# Soic8Pads.net
KiCad netlist of a schematic drawn in Altium Designer
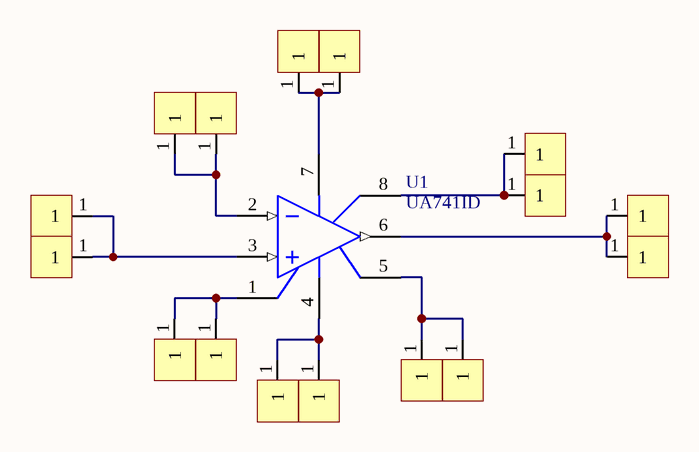
[diagram p0: Soic8Pads.SchDoc]

(export (version "E")
  (design (tool "Eeschema 10.0.6"))
  (components
    (comp (ref "U1")
      (value "UA741ID")
      (footprint "SO8_N")
      (description "General-Purpose Single Operational Amplifier")
      (fields (field (name "PUBLISHER") "Altium Limited"))
      (libsource (lib "ST Operational Amplifier") (part "UA741ID"))
    )
    (comp (ref "V5")
      (value "VIA40mil80mil")
      (footprint "VIA40mil80mil")
      (libsource (lib "") (part "VIA40mil80mil_2"))
    )
    (comp (ref "V6")
      (value "VIA40mil80mil")
      (footprint "VIA40mil80mil")
      (libsource (lib "") (part "VIA40mil80mil_2"))
    )
    (comp (ref "V9")
      (value "VIA40mil80mil")
      (footprint "VIA40mil80mil")
      (libsource (lib "") (part "VIA40mil80mil_2"))
    )
    (comp (ref "V10")
      (value "VIA40mil80mil")
      (footprint "VIA40mil80mil")
      (libsource (lib "") (part "VIA40mil80mil_2"))
    )
    (comp (ref "V13")
      (value "VIA40mil80mil")
      (footprint "VIA40mil80mil")
      (libsource (lib "") (part "VIA40mil80mil_1"))
    )
    (comp (ref "V15")
      (value "VIA40mil80mil")
      (footprint "VIA40mil80mil")
      (libsource (lib "") (part "VIA40mil80mil_1"))
    )
    (comp (ref "V17")
      (value "VIA40mil80mil")
      (footprint "VIA40mil80mil")
      (libsource (lib "") (part "VIA40mil80mil_3"))
    )
    (comp (ref "V18")
      (value "VIA40mil80mil")
      (footprint "VIA40mil80mil")
      (libsource (lib "") (part "VIA40mil80mil_1"))
    )
    (comp (ref "V21")
      (value "VIA40mil80mil")
      (footprint "VIA40mil80mil")
      (libsource (lib "") (part "VIA40mil80mil_3"))
    )
    (comp (ref "V22")
      (value "VIA40mil80mil")
      (footprint "VIA40mil80mil")
      (libsource (lib "") (part "VIA40mil80mil_1"))
    )
    (comp (ref "V25")
      (value "VIA40mil80mil")
      (footprint "VIA40mil80mil")
      (libsource (lib "AdamsParts") (part "VIA40mil80mil"))
    )
    (comp (ref "V26")
      (value "VIA40mil80mil")
      (footprint "VIA40mil80mil")
      (libsource (lib "AdamsParts") (part "VIA40mil80mil"))
    )
    (comp (ref "V29")
      (value "VIA40mil80mil")
      (footprint "VIA40mil80mil")
      (libsource (lib "AdamsParts") (part "VIA40mil80mil"))
    )
    (comp (ref "V30")
      (value "VIA40mil80mil")
      (footprint "VIA40mil80mil")
      (libsource (lib "AdamsParts") (part "VIA40mil80mil"))
    )
    (comp (ref "V33")
      (value "VIA40mil80mil")
      (footprint "VIA40mil80mil")
      (libsource (lib "AdamsParts") (part "VIA40mil80mil"))
    )
    (comp (ref "V34")
      (value "VIA40mil80mil")
      (footprint "VIA40mil80mil")
      (libsource (lib "AdamsParts") (part "VIA40mil80mil"))
    )
  )
  (nets
    (net (code "1") (name "Net-(U1-IN+)") (class "Default")
      (node (ref "U1") (pin "3") (pinfunction "IN+_3") (pintype "input"))
      (node (ref "V17") (pin "1") (pinfunction "1_1") (pintype "passive"))
      (node (ref "V21") (pin "1") (pinfunction "1_1") (pintype "passive"))
    )
    (net (code "2") (name "Net-(U1-IN-)") (class "Default")
      (node (ref "U1") (pin "2") (pinfunction "IN-_2") (pintype "input"))
      (node (ref "V10") (pin "1") (pinfunction "1_1") (pintype "passive"))
      (node (ref "V9") (pin "1") (pinfunction "1_1") (pintype "passive"))
    )
    (net (code "3") (name "Net-(U1-NC)") (class "Default")
      (node (ref "U1") (pin "8") (pinfunction "NC_8") (pintype "passive"))
      (node (ref "V13") (pin "1") (pinfunction "1_1") (pintype "passive"))
      (node (ref "V15") (pin "1") (pinfunction "1_1") (pintype "passive"))
    )
    (net (code "4") (name "Net-(U1-OS_NULL-Pad1)") (class "Default")
      (node (ref "U1") (pin "1") (pinfunction "OS_NULL_1") (pintype "passive"))
      (node (ref "V25") (pin "1") (pinfunction "1_1") (pintype "passive"))
      (node (ref "V26") (pin "1") (pinfunction "1_1") (pintype "passive"))
    )
    (net (code "5") (name "Net-(U1-OS_NULL-Pad5)") (class "Default")
      (node (ref "U1") (pin "5") (pinfunction "OS_NULL_5") (pintype "passive"))
      (node (ref "V29") (pin "1") (pinfunction "1_1") (pintype "passive"))
      (node (ref "V30") (pin "1") (pinfunction "1_1") (pintype "passive"))
    )
    (net (code "6") (name "Net-(U1-OUT)") (class "Default")
      (node (ref "U1") (pin "6") (pinfunction "OUT_6") (pintype "output"))
      (node (ref "V18") (pin "1") (pinfunction "1_1") (pintype "passive"))
      (node (ref "V22") (pin "1") (pinfunction "1_1") (pintype "passive"))
    )
    (net (code "7") (name "Net-(U1-V+)") (class "Default")
      (node (ref "U1") (pin "7") (pinfunction "V+_7") (pintype "power_in"))
      (node (ref "V5") (pin "1") (pinfunction "1_1") (pintype "passive"))
      (node (ref "V6") (pin "1") (pinfunction "1_1") (pintype "passive"))
    )
    (net (code "8") (name "Net-(U1-V-)") (class "Default")
      (node (ref "U1") (pin "4") (pinfunction "V-_4") (pintype "power_in"))
      (node (ref "V33") (pin "1") (pinfunction "1_1") (pintype "passive"))
      (node (ref "V34") (pin "1") (pinfunction "1_1") (pintype "passive"))
    )
  )
)
